# ACESDS1307BoBV3.net
KiCad netlist of a schematic drawn in EAGLE
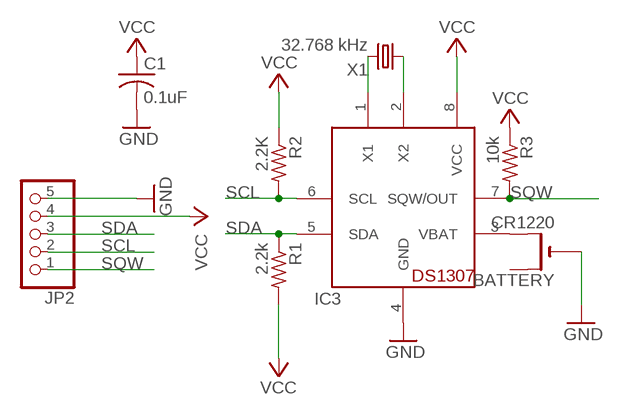
[diagram p0: schematic, sheet 1]

(export (version "E")
  (design (tool "Eeschema 10.0.6"))
  (components
    (comp (ref "BATTERY")
      (value "CR1220")
      (footprint "eagle-import:CR1220-THM")
      (libsource (lib "eagle-import") (part "CR1220THM"))
    )
    (comp (ref "C1")
      (value "0.1uF")
      (footprint "eagle-import:C025-025X050")
      (libsource (lib "eagle-import") (part "C-US025-025X050"))
    )
    (comp (ref "IC3")
      (value "DS1307")
      (footprint "eagle-import:DIL08")
      (libsource (lib "eagle-import") (part "DS1307"))
    )
    (comp (ref "JP2")
      (value "PINHD-1X5")
      (footprint "eagle-import:1X05")
      (libsource (lib "eagle-import") (part "PINHD-1X5"))
    )
    (comp (ref "R1")
      (value "2.2k")
      (footprint "eagle-import:0207_10")
      (libsource (lib "eagle-import") (part "R-US_0207/10"))
    )
    (comp (ref "R2")
      (value "2.2K")
      (footprint "eagle-import:0207_10")
      (libsource (lib "eagle-import") (part "R-US_0207/10"))
    )
    (comp (ref "R3")
      (value "10k")
      (footprint "eagle-import:0207_10")
      (libsource (lib "eagle-import") (part "R-US_0207/10"))
    )
    (comp (ref "X1")
      (value "32.768 kHz")
      (footprint "eagle-import:TC38H")
      (libsource (lib "eagle-import") (part "CRYTALTC38H"))
    )
  )
  (nets
    (net (code "1") (name "/SCL") (class "Default")
      (node (ref "IC3") (pin "6") (pinfunction "SCL_6") (pintype "bidirectional"))
      (node (ref "JP2") (pin "2") (pinfunction "2_2") (pintype "passive"))
      (node (ref "R2") (pin "2") (pinfunction "2_2") (pintype "passive"))
    )
    (net (code "2") (name "/SDA") (class "Default")
      (node (ref "IC3") (pin "5") (pinfunction "SDA_5") (pintype "bidirectional"))
      (node (ref "JP2") (pin "3") (pinfunction "3_3") (pintype "passive"))
      (node (ref "R1") (pin "1") (pinfunction "1_1") (pintype "passive"))
    )
    (net (code "3") (name "/SQW") (class "Default")
      (node (ref "IC3") (pin "7") (pinfunction "SQW/OUT_7") (pintype "bidirectional"))
      (node (ref "JP2") (pin "1") (pinfunction "1_1") (pintype "passive"))
      (node (ref "R3") (pin "2") (pinfunction "2_2") (pintype "passive"))
    )
    (net (code "4") (name "GND") (class "Default")
      (node (ref "BATTERY") (pin "-") (pinfunction "-_-") (pintype "passive"))
      (node (ref "C1") (pin "2") (pinfunction "2_2") (pintype "passive"))
      (node (ref "IC3") (pin "4") (pinfunction "GND_4") (pintype "power_in"))
      (node (ref "JP2") (pin "5") (pinfunction "5_5") (pintype "passive"))
    )
    (net (code "5") (name "Net-(BATTERY-+1)") (class "Default")
      (node (ref "BATTERY") (pin "+2") (pinfunction "+1_+2") (pintype "passive"))
      (node (ref "IC3") (pin "3") (pinfunction "VBAT_3") (pintype "power_in"))
    )
    (net (code "6") (name "Net-(IC3-X1)") (class "Default")
      (node (ref "IC3") (pin "1") (pinfunction "X1_1") (pintype "passive"))
      (node (ref "X1") (pin "2") (pinfunction "2_2") (pintype "passive"))
    )
    (net (code "7") (name "Net-(IC3-X2)") (class "Default")
      (node (ref "IC3") (pin "2") (pinfunction "X2_2") (pintype "passive"))
      (node (ref "X1") (pin "1") (pinfunction "1_1") (pintype "passive"))
    )
    (net (code "8") (name "VCC") (class "Default")
      (node (ref "C1") (pin "1") (pinfunction "1_1") (pintype "passive"))
      (node (ref "IC3") (pin "8") (pinfunction "VCC_8") (pintype "power_in"))
      (node (ref "JP2") (pin "4") (pinfunction "4_4") (pintype "passive"))
      (node (ref "R1") (pin "2") (pinfunction "2_2") (pintype "passive"))
      (node (ref "R2") (pin "1") (pinfunction "1_1") (pintype "passive"))
      (node (ref "R3") (pin "1") (pinfunction "1_1") (pintype "passive"))
    )
    (net (code "9") (name "unconnected-(BATTERY-+-Pad+1)") (class "Default")
      (node (ref "BATTERY") (pin "+1") (pinfunction "+_+1") (pintype "passive"))
    )
  )
)
